# sFMC98_v3.net
KiCad netlist of a schematic drawn in Altium Designer
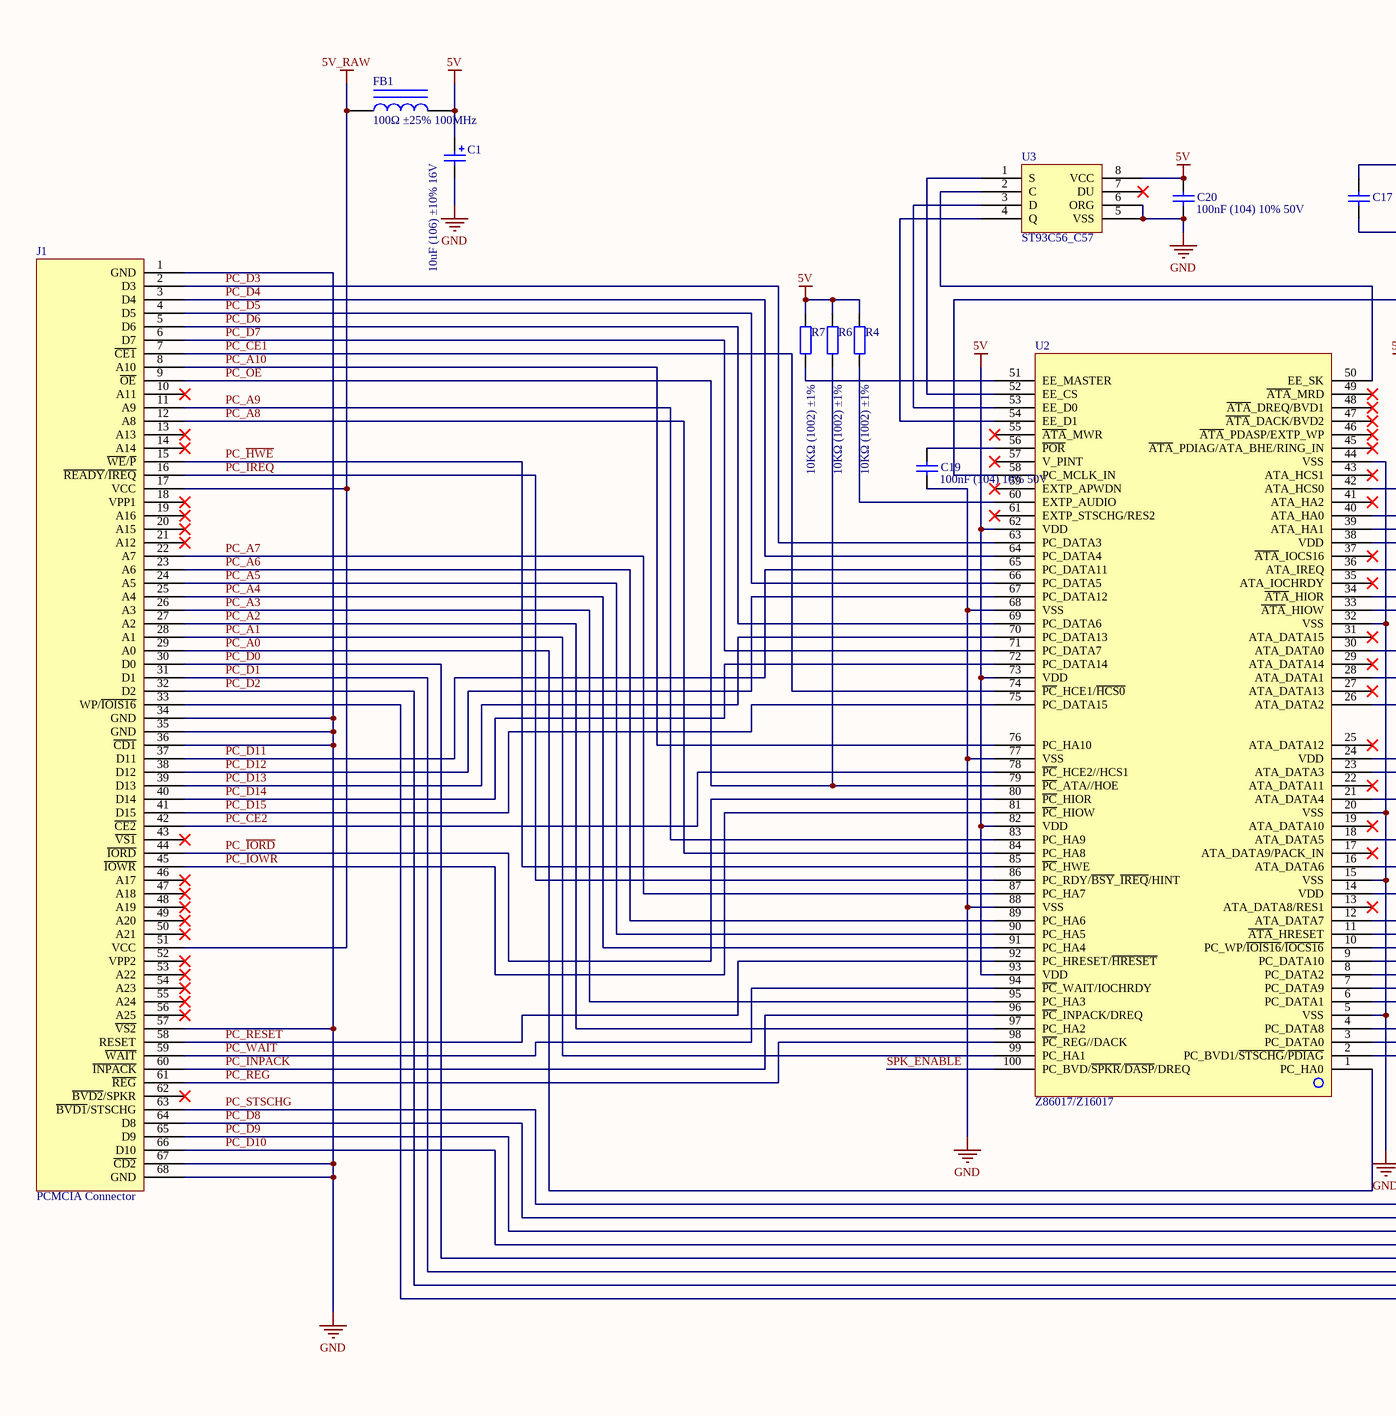
[diagram p0: sFMC98_v3.SchDoc, left]
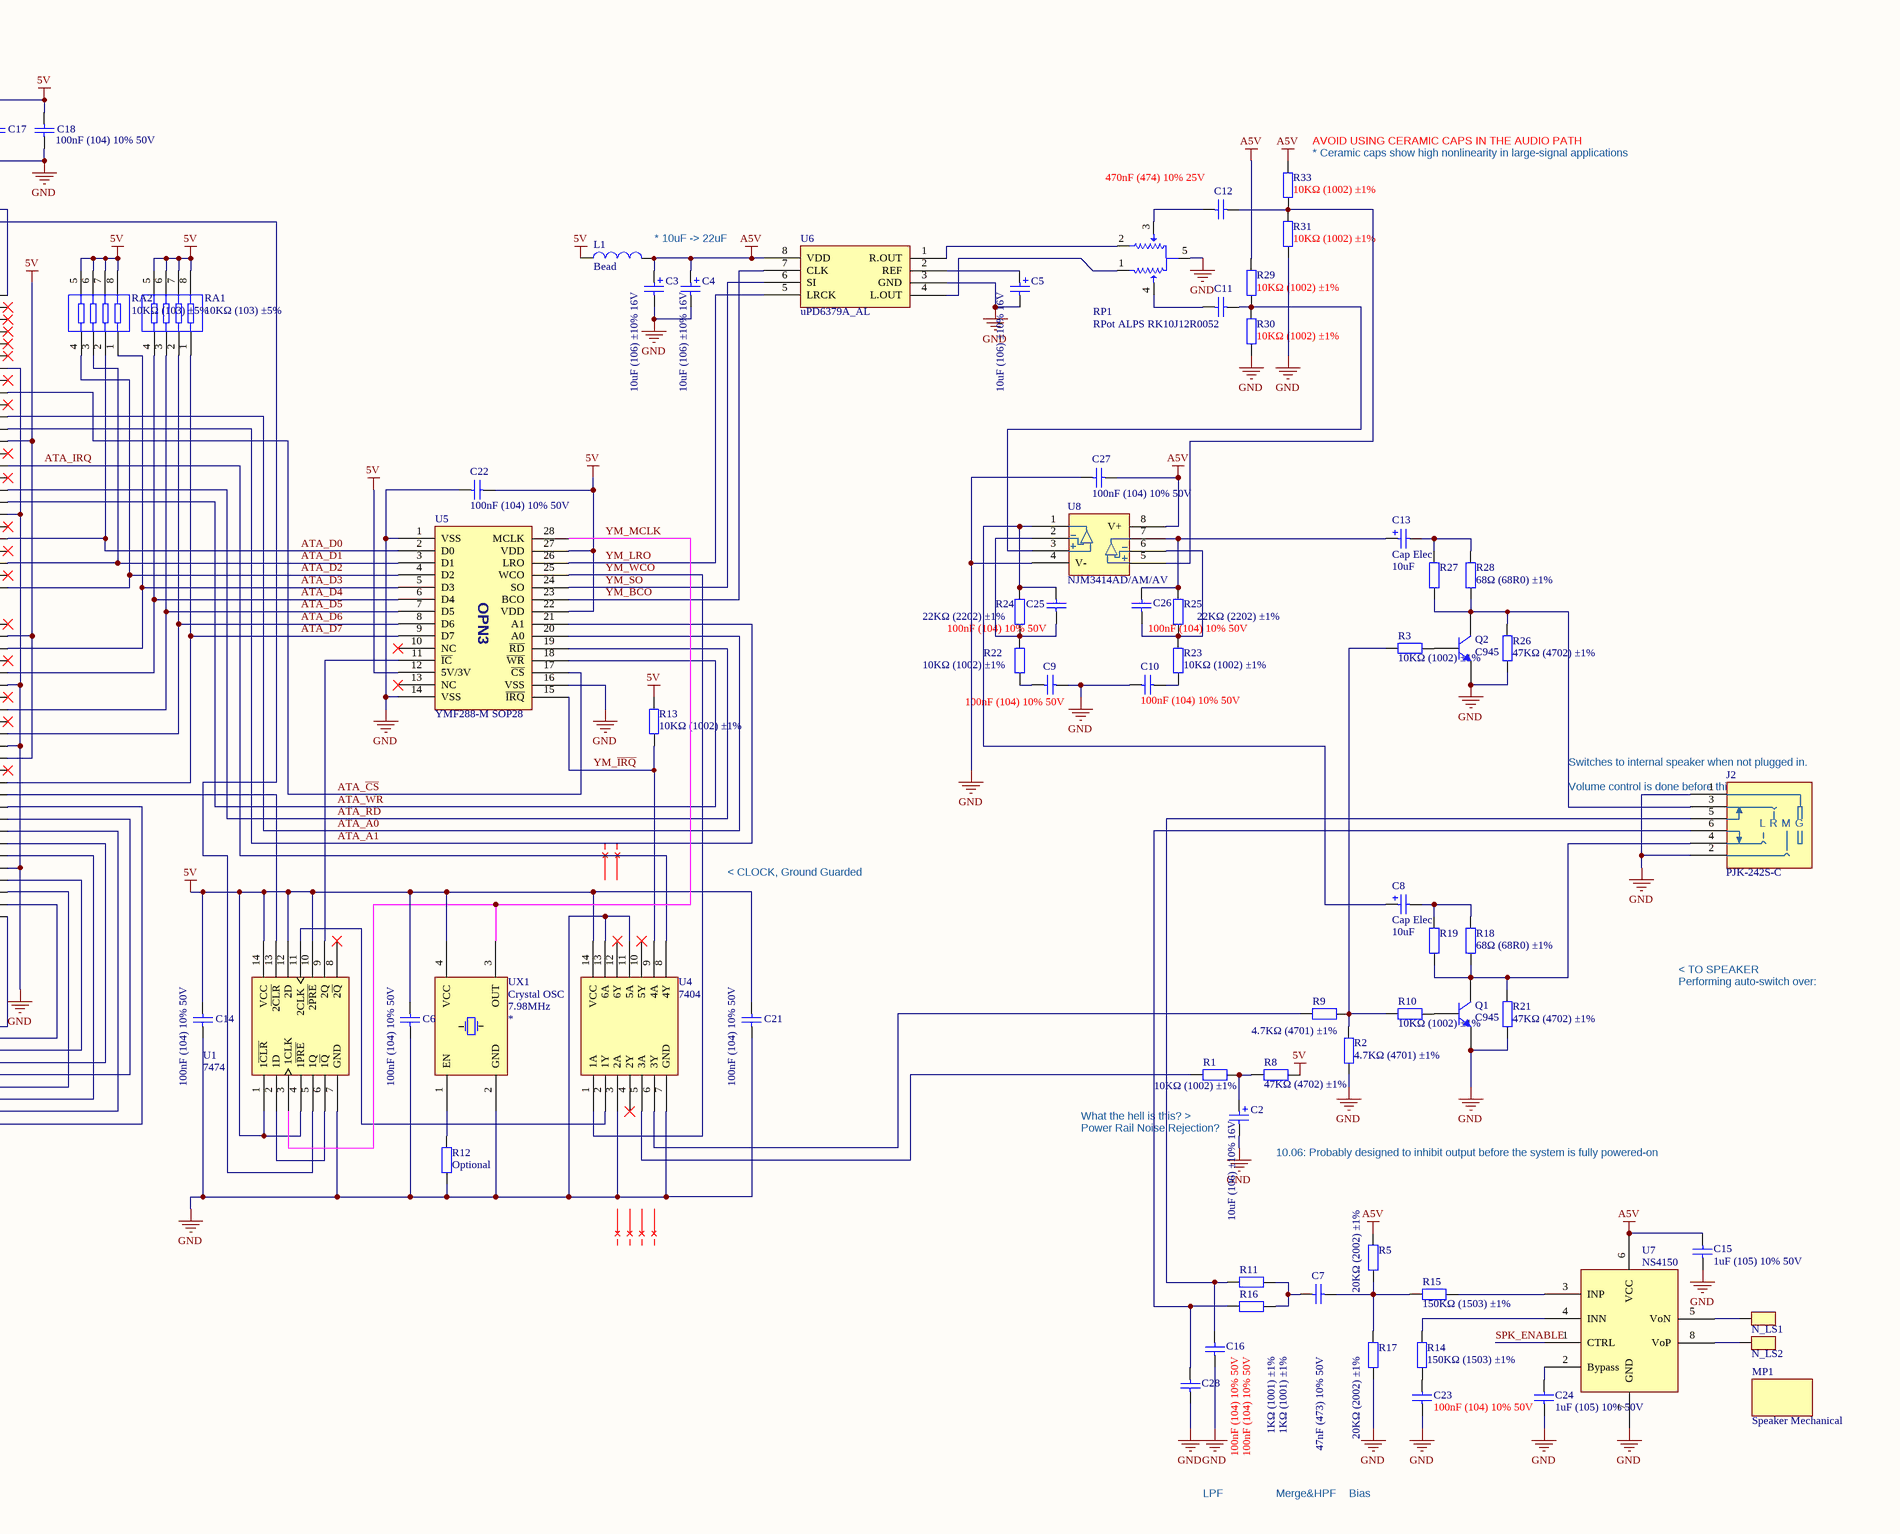
[diagram p1: sFMC98_v3.SchDoc, right]

(export (version "E")
  (design (tool "Eeschema 10.0.6"))
  (components
    (comp (ref "C1")
      (value "10uF (106) ±10% 16V")
      (footprint "CASE-A_3216")
      (description "钽电容")
      (libsource (lib "JLC_Cap") (part "3216 10uF (106) 10% 16V"))
    )
    (comp (ref "C2")
      (value "10uF (106) ±10% 16V")
      (footprint "CASE-A_3216")
      (description "钽电容")
      (libsource (lib "JLC_Cap") (part "3216 10uF (106) 10% 16V"))
    )
    (comp (ref "C3")
      (value "10uF (106) ±10% 16V")
      (footprint "CASE-A_3216")
      (description "钽电容")
      (libsource (lib "JLC_Cap") (part "3216 10uF (106) 10% 16V"))
    )
    (comp (ref "C4")
      (value "10uF (106) ±10% 16V")
      (footprint "CASE-A_3216")
      (description "钽电容")
      (libsource (lib "JLC_Cap") (part "3216 10uF (106) 10% 16V"))
    )
    (comp (ref "C5")
      (value "10uF (106) ±10% 16V")
      (footprint "CASE-A_3216")
      (description "钽电容")
      (libsource (lib "JLC_Cap") (part "3216 10uF (106) 10% 16V"))
    )
    (comp (ref "C6")
      (value "100nF (104) 10% 50V")
      (footprint "0603_C")
      (description "贴片电容")
      (libsource (lib "JLC_Cap") (part "0603 100nF (104) 10% 50V"))
    )
    (comp (ref "C7")
      (value "47nF (473) 10% 50V")
      (footprint "0603_C")
      (description "贴片电容")
      (libsource (lib "JLC_Cap") (part "0603 47nF (473) 10% 50V"))
    )
    (comp (ref "C8")
      (value "Cap Elec")
      (footprint "C-RB-4_5MM_Cutout")
      (description "Polarized Capacitor (Surface Mount)")
      (fields (field (name "ALTIUM_VALUE") "10uF") (field (name "PUBLISHER") "Altium Limited"))
      (libsource (lib "DiscreteRF") (part "Cap Pol3"))
    )
    (comp (ref "C9")
      (value "100nF (104) 10% 50V")
      (footprint "0603_C")
      (description "贴片电容")
      (libsource (lib "JLC_Cap") (part "0603 100nF (104) 10% 50V"))
    )
    (comp (ref "C10")
      (value "100nF (104) 10% 50V")
      (footprint "0603_C")
      (description "贴片电容")
      (libsource (lib "JLC_Cap") (part "0603 100nF (104) 10% 50V"))
    )
    (comp (ref "C11")
      (value "470nF (474) 10% 25V")
      (footprint "0603_C")
      (description "贴片电容")
      (libsource (lib "JLC_Cap") (part "0603 470nF (474) 10% 25V"))
    )
    (comp (ref "C12")
      (value "470nF (474) 10% 25V")
      (footprint "0603_C")
      (description "贴片电容")
      (libsource (lib "JLC_Cap") (part "0603 470nF (474) 10% 25V"))
    )
    (comp (ref "C13")
      (value "Cap Elec")
      (footprint "C-RB-4_5MM_Cutout")
      (description "Polarized Capacitor (Surface Mount)")
      (fields (field (name "ALTIUM_VALUE") "10uF") (field (name "PUBLISHER") "Altium Limited"))
      (libsource (lib "DiscreteRF") (part "Cap Pol3"))
    )
    (comp (ref "C14")
      (value "100nF (104) 10% 50V")
      (footprint "0603_C")
      (description "贴片电容")
      (libsource (lib "JLC_Cap") (part "0603 100nF (104) 10% 50V"))
    )
    (comp (ref "C15")
      (value "1uF (105) 10% 50V")
      (footprint "0603_C")
      (description "贴片电容")
      (libsource (lib "JLC_Cap") (part "0603 1uF (105) 10% 50V"))
    )
    (comp (ref "C16")
      (value "100nF (104) 10% 50V")
      (footprint "0603_C")
      (description "贴片电容")
      (libsource (lib "JLC_Cap") (part "0603 100nF (104) 10% 50V"))
    )
    (comp (ref "C17")
      (value "100nF (104) 10% 50V")
      (footprint "0603_C")
      (description "贴片电容")
      (libsource (lib "JLC_Cap") (part "0603 100nF (104) 10% 50V"))
    )
    (comp (ref "C18")
      (value "100nF (104) 10% 50V")
      (footprint "0603_C")
      (description "贴片电容")
      (libsource (lib "JLC_Cap") (part "0603 100nF (104) 10% 50V"))
    )
    (comp (ref "C19")
      (value "100nF (104) 10% 50V")
      (footprint "0603_C")
      (description "贴片电容")
      (libsource (lib "JLC_Cap") (part "0603 100nF (104) 10% 50V"))
    )
    (comp (ref "C20")
      (value "100nF (104) 10% 50V")
      (footprint "0603_C")
      (description "贴片电容")
      (libsource (lib "JLC_Cap") (part "0603 100nF (104) 10% 50V"))
    )
    (comp (ref "C21")
      (value "100nF (104) 10% 50V")
      (footprint "0603_C")
      (description "贴片电容")
      (libsource (lib "JLC_Cap") (part "0603 100nF (104) 10% 50V"))
    )
    (comp (ref "C22")
      (value "100nF (104) 10% 50V")
      (footprint "0603_C")
      (description "贴片电容")
      (libsource (lib "JLC_Cap") (part "0603 100nF (104) 10% 50V"))
    )
    (comp (ref "C23")
      (value "100nF (104) 10% 50V")
      (footprint "0603_C")
      (description "贴片电容")
      (libsource (lib "JLC_Cap") (part "0603 100nF (104) 10% 50V"))
    )
    (comp (ref "C24")
      (value "1uF (105) 10% 50V")
      (footprint "0603_C")
      (description "贴片电容")
      (libsource (lib "JLC_Cap") (part "0603 1uF (105) 10% 50V"))
    )
    (comp (ref "C25")
      (value "100nF (104) 10% 50V")
      (footprint "0603_C")
      (description "贴片电容")
      (libsource (lib "JLC_Cap") (part "0603 100nF (104) 10% 50V"))
    )
    (comp (ref "C26")
      (value "100nF (104) 10% 50V")
      (footprint "0603_C")
      (description "贴片电容")
      (libsource (lib "JLC_Cap") (part "0603 100nF (104) 10% 50V"))
    )
    (comp (ref "C27")
      (value "100nF (104) 10% 50V")
      (footprint "0603_C")
      (description "贴片电容")
      (libsource (lib "JLC_Cap") (part "0603 100nF (104) 10% 50V"))
    )
    (comp (ref "C28")
      (value "100nF (104) 10% 50V")
      (footprint "0603_C")
      (description "贴片电容")
      (libsource (lib "JLC_Cap") (part "0603 100nF (104) 10% 50V"))
    )
    (comp (ref "FB1")
      (value "100Ω ±25% 100MHz")
      (footprint "0805_L")
      (description "贴片磁珠")
      (libsource (lib "JLC_IUD") (part "0805 100Ω 25% 100MHz"))
    )
    (comp (ref "J1")
      (value "PCMCIA Connector")
      (footprint "PCF-SMT-K1")
      (libsource (lib "PrimaryLIB1") (part "PCMCIA_Conn"))
    )
    (comp (ref "J2")
      (value "PJK-242S-C")
      (footprint "PJK-242S-C")
      (description "2.5mm Headphone Jack")
      (libsource (lib "PrimaryLIB1") (part "PJK-242S-C"))
    )
    (comp (ref "L1")
      (value "Bead")
      (footprint "L2012X10N_LQW21")
      (description "Inductor")
      (fields (field (name "PUBLISHER") "Altium Limited"))
      (libsource (lib "DiscreteRF") (part "Inductor"))
    )
    (comp (ref "MP1")
      (value "Speaker Mechanical")
      (footprint "ZT097")
      (libsource (lib "PrimaryLIB1") (part "Mechanical"))
    )
    (comp (ref "N_LS1")
      (value "PAD")
      (footprint "Pad")
      (description "Generic Pad")
      (libsource (lib "PrimaryLIB0") (part "PAD"))
    )
    (comp (ref "N_LS2")
      (value "PAD")
      (footprint "Pad")
      (description "Generic Pad")
      (libsource (lib "PrimaryLIB0") (part "PAD"))
    )
    (comp (ref "Q1")
      (value "C945")
      (footprint "SOT-23(SOT-23-3)")
      (description "三极管")
      (libsource (lib "JLC_Transistor_NPN") (part "SOT-23 SS8050 Y1"))
    )
    (comp (ref "Q2")
      (value "C945")
      (footprint "SOT-23(SOT-23-3)")
      (description "三极管")
      (libsource (lib "JLC_Transistor_NPN") (part "SOT-23 SS8050 Y1"))
    )
    (comp (ref "R1")
      (value "10KΩ (1002) ±1%")
      (footprint "0603_R")
      (description "贴片电阻")
      (libsource (lib "") (part "0603 10KΩ (1002) 1%_1"))
    )
    (comp (ref "R2")
      (value "4.7KΩ (4701) ±1%")
      (footprint "0603_R")
      (description "贴片电阻")
      (libsource (lib "") (part "0603 4.7KΩ (4701) 1%_1"))
    )
    (comp (ref "R3")
      (value "10KΩ (1002) ±1%")
      (footprint "0603_R")
      (description "贴片电阻")
      (libsource (lib "") (part "0603 10KΩ (1002) 1%_1"))
    )
    (comp (ref "R4")
      (value "10KΩ (1002) ±1%")
      (footprint "0603_R")
      (description "贴片电阻")
      (libsource (lib "JLC_RES") (part "0603 10KΩ (1002) 1%"))
    )
    (comp (ref "R5")
      (value "20KΩ (2002) ±1%")
      (footprint "0603_R")
      (description "贴片电阻")
      (libsource (lib "JLC_RES") (part "0603 20KΩ (2002) 1%"))
    )
    (comp (ref "R6")
      (value "10KΩ (1002) ±1%")
      (footprint "0603_R")
      (description "贴片电阻")
      (libsource (lib "JLC_RES") (part "0603 10KΩ (1002) 1%"))
    )
    (comp (ref "R7")
      (value "10KΩ (1002) ±1%")
      (footprint "0603_R")
      (description "贴片电阻")
      (libsource (lib "JLC_RES") (part "0603 10KΩ (1002) 1%"))
    )
    (comp (ref "R8")
      (value "47KΩ (4702) ±1%")
      (footprint "0603_R")
      (description "贴片电阻")
      (libsource (lib "") (part "0603 47KΩ (4702) 1%_1"))
    )
    (comp (ref "R9")
      (value "4.7KΩ (4701) ±1%")
      (footprint "0603_R")
      (description "贴片电阻")
      (libsource (lib "JLC_RES") (part "0603 4.7KΩ (4701) 1%"))
    )
    (comp (ref "R10")
      (value "10KΩ (1002) ±1%")
      (footprint "0603_R")
      (description "贴片电阻")
      (libsource (lib "") (part "0603 10KΩ (1002) 1%_1"))
    )
    (comp (ref "R11")
      (value "1KΩ (1001) ±1%")
      (footprint "0603_R")
      (description "贴片电阻")
      (libsource (lib "JLC_RES") (part "0603 1KΩ (1001) 1%"))
    )
    (comp (ref "R12")
      (value "Optional")
      (footprint "0603_R")
      (description "贴片电阻")
      (libsource (lib "JLC_RES") (part "0603 10KΩ (1002) 1%"))
    )
    (comp (ref "R13")
      (value "10KΩ (1002) ±1%")
      (footprint "0603_R")
      (description "贴片电阻")
      (libsource (lib "JLC_RES") (part "0603 10KΩ (1002) 1%"))
    )
    (comp (ref "R14")
      (value "150KΩ (1503) ±1%")
      (footprint "0603_R")
      (description "贴片电阻")
      (libsource (lib "JLC_RES") (part "0603 150KΩ (1503) 1%"))
    )
    (comp (ref "R15")
      (value "150KΩ (1503) ±1%")
      (footprint "0603_R")
      (description "贴片电阻")
      (libsource (lib "") (part "0603 150KΩ (1503) 1%_1"))
    )
    (comp (ref "R16")
      (value "1KΩ (1001) ±1%")
      (footprint "0603_R")
      (description "贴片电阻")
      (libsource (lib "JLC_RES") (part "0603 1KΩ (1001) 1%"))
    )
    (comp (ref "R17")
      (value "20KΩ (2002) ±1%")
      (footprint "0603_R")
      (description "贴片电阻")
      (libsource (lib "JLC_RES") (part "0603 20KΩ (2002) 1%"))
    )
    (comp (ref "R18")
      (value "68Ω (68R0) ±1%")
      (footprint "0603_R")
      (description "贴片电阻")
      (libsource (lib "JLC_RES") (part "0603 68Ω (68R0) 1%"))
    )
    (comp (ref "R19")
      (value "68Ω (68R0) ±1%")
      (footprint "0603_R")
      (description "贴片电阻")
      (libsource (lib "JLC_RES") (part "0603 68Ω (68R0) 1%"))
    )
    (comp (ref "R21")
      (value "47KΩ (4702) ±1%")
      (footprint "0603_R")
      (description "贴片电阻")
      (libsource (lib "JLC_RES") (part "0603 47KΩ (4702) 1%"))
    )
    (comp (ref "R22")
      (value "10KΩ (1002) ±1%")
      (footprint "0603_R")
      (description "贴片电阻")
      (libsource (lib "JLC_RES") (part "0603 10KΩ (1002) 1%"))
    )
    (comp (ref "R23")
      (value "10KΩ (1002) ±1%")
      (footprint "0603_R")
      (description "贴片电阻")
      (libsource (lib "JLC_RES") (part "0603 10KΩ (1002) 1%"))
    )
    (comp (ref "R24")
      (value "22KΩ (2202) ±1%")
      (footprint "0603_R")
      (description "贴片电阻")
      (libsource (lib "JLC_RES") (part "0603 22KΩ (2202) 1%"))
    )
    (comp (ref "R25")
      (value "22KΩ (2202) ±1%")
      (footprint "0603_R")
      (description "贴片电阻")
      (libsource (lib "JLC_RES") (part "0603 22KΩ (2202) 1%"))
    )
    (comp (ref "R26")
      (value "47KΩ (4702) ±1%")
      (footprint "0603_R")
      (description "贴片电阻")
      (libsource (lib "JLC_RES") (part "0603 47KΩ (4702) 1%"))
    )
    (comp (ref "R27")
      (value "68Ω (68R0) ±1%")
      (footprint "0603_R")
      (description "贴片电阻")
      (libsource (lib "JLC_RES") (part "0603 68Ω (68R0) 1%"))
    )
    (comp (ref "R28")
      (value "68Ω (68R0) ±1%")
      (footprint "0603_R")
      (description "贴片电阻")
      (libsource (lib "JLC_RES") (part "0603 68Ω (68R0) 1%"))
    )
    (comp (ref "R29")
      (value "10KΩ (1002) ±1%")
      (footprint "0603_R")
      (description "贴片电阻")
      (libsource (lib "JLC_RES") (part "0603 10KΩ (1002) 1%"))
    )
    (comp (ref "R30")
      (value "10KΩ (1002) ±1%")
      (footprint "0603_R")
      (description "贴片电阻")
      (libsource (lib "JLC_RES") (part "0603 10KΩ (1002) 1%"))
    )
    (comp (ref "R31")
      (value "10KΩ (1002) ±1%")
      (footprint "0603_R")
      (description "贴片电阻")
      (libsource (lib "JLC_RES") (part "0603 10KΩ (1002) 1%"))
    )
    (comp (ref "R33")
      (value "10KΩ (1002) ±1%")
      (footprint "0603_R")
      (description "贴片电阻")
      (libsource (lib "JLC_RES") (part "0603 10KΩ (1002) 1%"))
    )
    (comp (ref "RA1")
      (value "10KΩ (103) ±5%")
      (footprint "0603_Rx4")
      (description "贴片排阻")
      (libsource (lib "JLC_RES") (part "0603*4  10KΩ (103) 5%"))
    )
    (comp (ref "RA2")
      (value "10KΩ (103) ±5%")
      (footprint "0603_Rx4")
      (description "贴片排阻")
      (libsource (lib "JLC_RES") (part "0603*4  10KΩ (103) 5%"))
    )
    (comp (ref "RP1")
      (value "RPot ALPS RK10J12R0052")
      (footprint "RPot_RK10J12R_ALPS")
      (description "ALPS Taper Type C, Dual Unit")
      (libsource (lib "PrimaryLIB1") (part "RPot_ALPS_C2"))
    )
    (comp (ref "U1")
      (value "7474")
      (footprint "TSSOP14_TSOP65P640X120-14N")
      (description "Dual D-Type Positive-Edge-Triggered Flip-Flops With Preset And Clear")
      (libsource (lib "7400") (part "7474_J_N_1"))
    )
    (comp (ref "U2")
      (value "Z86017/Z16017")
      (footprint "VQFP100_TSQFP50P1600X1600X160-100N")
      (libsource (lib "PrimaryLIB1") (part "ZX6017"))
    )
    (comp (ref "U3")
      (value "ST93C56_C57")
      (footprint "SOIC-8 NB")
      (description "2K (128 x 16 or 256 x 8) SERIAL MICROWIRE EEPROM")
      (libsource (lib "PrimaryLIB1") (part "ST93C56_C57"))
    )
    (comp (ref "U4")
      (value "7404")
      (footprint "TSSOP14_TSOP65P640X120-14N")
      (description "Hex Inverter")
      (libsource (lib "7400") (part "7404_J_N_1"))
    )
    (comp (ref "U5")
      (value "YMF288-M SOP28")
      (footprint "SOP127P1030X265-28N")
      (libsource (lib "Audio") (part "YMF288_M"))
    )
    (comp (ref "U6")
      (value "uPD6379A_AL")
      (footprint "DMP8_SOIC127P680X175-8N")
      (description "2-CHANNEL 16-BIT D/A CONVERTER FOR AUDIO APPLICATION")
      (libsource (lib "Audio") (part "uPD6379A_AL"))
    )
    (comp (ref "U7")
      (value "NS4150")
      (footprint "MS8")
      (description "超低 EMI、无需滤波器、3W 单声道 D 类音频功放")
      (libsource (lib "PrimaryLIB1") (part "NS4150"))
    )
    (comp (ref "U8")
      (value "NJM3414AD/AM/AV")
      (footprint "DMP8_SOIC127P680X175-8N")
      (description "Single-Supply Dual High Current Operational Amplifier")
      (libsource (lib "PrimaryLIB1") (part "NJM3414AD_AM_AV_1"))
    )
    (comp (ref "UX1")
      (value "Crystal OSC")
      (footprint "SMD-3225_4P")
      (fields (field (name "FREQ") "7.98MHz") (field (name "TYPE") "*"))
      (libsource (lib "PrimaryLIB1") (part "XTAL_OSC"))
    )
  )
  (nets
    (net (code "1") (name "/ATA_A0") (class "Default")
      (node (ref "U2") (pin "40") (pinfunction "ATA_HA0_40") (pintype "passive"))
      (node (ref "U5") (pin "20") (pinfunction "A0_20") (pintype "passive"))
    )
    (net (code "2") (name "/ATA_A1") (class "Default")
      (node (ref "U2") (pin "39") (pinfunction "ATA_HA1_39") (pintype "passive"))
      (node (ref "U5") (pin "21") (pinfunction "A1_21") (pintype "passive"))
    )
    (net (code "3") (name "/ATA_D0") (class "Default")
      (node (ref "RA2") (pin "2") (pinfunction "2_2") (pintype "passive"))
      (node (ref "U2") (pin "30") (pinfunction "ATA_DATA0_30") (pintype "passive"))
      (node (ref "U5") (pin "2") (pinfunction "D0_2") (pintype "passive"))
    )
    (net (code "4") (name "/ATA_D1") (class "Default")
      (node (ref "RA2") (pin "3") (pinfunction "3_3") (pintype "passive"))
      (node (ref "U2") (pin "28") (pinfunction "ATA_DATA1_28") (pintype "passive"))
      (node (ref "U5") (pin "3") (pinfunction "D1_3") (pintype "passive"))
    )
    (net (code "5") (name "/ATA_D2") (class "Default")
      (node (ref "RA2") (pin "4") (pinfunction "4_4") (pintype "passive"))
      (node (ref "U2") (pin "26") (pinfunction "ATA_DATA2_26") (pintype "passive"))
      (node (ref "U5") (pin "4") (pinfunction "D2_4") (pintype "passive"))
    )
    (net (code "6") (name "/ATA_D3") (class "Default")
      (node (ref "RA2") (pin "1") (pinfunction "1_1") (pintype "passive"))
      (node (ref "U2") (pin "23") (pinfunction "ATA_DATA3_23") (pintype "passive"))
      (node (ref "U5") (pin "5") (pinfunction "D3_5") (pintype "passive"))
    )
    (net (code "7") (name "/ATA_D4") (class "Default")
      (node (ref "RA1") (pin "4") (pinfunction "4_4") (pintype "passive"))
      (node (ref "U2") (pin "21") (pinfunction "ATA_DATA4_21") (pintype "passive"))
      (node (ref "U5") (pin "6") (pinfunction "D4_6") (pintype "passive"))
    )
    (net (code "8") (name "/ATA_D5") (class "Default")
      (node (ref "RA1") (pin "3") (pinfunction "3_3") (pintype "passive"))
      (node (ref "U2") (pin "18") (pinfunction "ATA_DATA5_18") (pintype "passive"))
      (node (ref "U5") (pin "7") (pinfunction "D5_7") (pintype "passive"))
    )
    (net (code "9") (name "/ATA_D6") (class "Default")
      (node (ref "RA1") (pin "2") (pinfunction "2_2") (pintype "passive"))
      (node (ref "U2") (pin "16") (pinfunction "ATA_DATA6_16") (pintype "passive"))
      (node (ref "U5") (pin "8") (pinfunction "D6_8") (pintype "passive"))
    )
    (net (code "10") (name "/ATA_D7") (class "Default")
      (node (ref "RA1") (pin "1") (pinfunction "1_1") (pintype "passive"))
      (node (ref "U2") (pin "12") (pinfunction "ATA_DATA7_12") (pintype "passive"))
      (node (ref "U5") (pin "9") (pinfunction "D7_9") (pintype "passive"))
    )
    (net (code "11") (name "/ATA_IRQ") (class "Default")
      (node (ref "U2") (pin "36") (pinfunction "ATA_IREQ_36") (pintype "passive"))
      (node (ref "U4") (pin "8") (pinfunction "4Y_8") (pintype "passive"))
    )
    (net (code "12") (name "/ATA_~{CS}") (class "Default")
      (node (ref "U2") (pin "42") (pinfunction "ATA_HCS0_42") (pintype "passive"))
      (node (ref "U5") (pin "17") (pinfunction "~{CS}_17") (pintype "passive"))
    )
    (net (code "13") (name "/ATA_~{RD}") (class "Default")
      (node (ref "U2") (pin "34") (pinfunction "~{ATA}_HIOR_34") (pintype "passive"))
      (node (ref "U5") (pin "19") (pinfunction "~{RD}_19") (pintype "passive"))
    )
    (net (code "14") (name "/ATA_~{WR}") (class "Default")
      (node (ref "U2") (pin "33") (pinfunction "~{ATA}_HIOW_33") (pintype "passive"))
      (node (ref "U5") (pin "18") (pinfunction "~{WR}_18") (pintype "passive"))
    )
    (net (code "15") (name "/PC_A0") (class "Default")
      (node (ref "J1") (pin "29") (pinfunction "A0_29") (pintype "passive"))
      (node (ref "U2") (pin "1") (pinfunction "PC_HA0_1") (pintype "passive"))
    )
    (net (code "16") (name "/PC_A1") (class "Default")
      (node (ref "J1") (pin "28") (pinfunction "A1_28") (pintype "passive"))
      (node (ref "U2") (pin "99") (pinfunction "PC_HA1_99") (pintype "passive"))
    )
    (net (code "17") (name "/PC_A2") (class "Default")
      (node (ref "J1") (pin "27") (pinfunction "A2_27") (pintype "passive"))
      (node (ref "U2") (pin "97") (pinfunction "PC_HA2_97") (pintype "passive"))
    )
    (net (code "18") (name "/PC_A3") (class "Default")
      (node (ref "J1") (pin "26") (pinfunction "A3_26") (pintype "passive"))
      (node (ref "U2") (pin "95") (pinfunction "PC_HA3_95") (pintype "passive"))
    )
    (net (code "19") (name "/PC_A4") (class "Default")
      (node (ref "J1") (pin "25") (pinfunction "A4_25") (pintype "passive"))
      (node (ref "U2") (pin "91") (pinfunction "PC_HA4_91") (pintype "passive"))
    )
    (net (code "20") (name "/PC_A5") (class "Default")
      (node (ref "J1") (pin "24") (pinfunction "A5_24") (pintype "passive"))
      (node (ref "U2") (pin "90") (pinfunction "PC_HA5_90") (pintype "passive"))
    )
    (net (code "21") (name "/PC_A6") (class "Default")
      (node (ref "J1") (pin "23") (pinfunction "A6_23") (pintype "passive"))
      (node (ref "U2") (pin "89") (pinfunction "PC_HA6_89") (pintype "passive"))
    )
    (net (code "22") (name "/PC_A7") (class "Default")
      (node (ref "J1") (pin "22") (pinfunction "A7_22") (pintype "passive"))
      (node (ref "U2") (pin "87") (pinfunction "PC_HA7_87") (pintype "passive"))
    )
    (net (code "23") (name "/PC_A8") (class "Default")
      (node (ref "J1") (pin "12") (pinfunction "A8_12") (pintype "passive"))
      (node (ref "U2") (pin "84") (pinfunction "PC_HA8_84") (pintype "passive"))
    )
    (net (code "24") (name "/PC_A9") (class "Default")
      (node (ref "J1") (pin "11") (pinfunction "A9_11") (pintype "passive"))
      (node (ref "U2") (pin "83") (pinfunction "PC_HA9_83") (pintype "passive"))
    )
    (net (code "25") (name "/PC_A10") (class "Default")
      (node (ref "J1") (pin "8") (pinfunction "A10_8") (pintype "passive"))
      (node (ref "U2") (pin "76") (pinfunction "PC_HA10_76") (pintype "passive"))
    )
    (net (code "26") (name "/PC_D0") (class "Default")
      (node (ref "J1") (pin "30") (pinfunction "D0_30") (pintype "passive"))
      (node (ref "U2") (pin "3") (pinfunction "PC_DATA0_3") (pintype "passive"))
    )
    (net (code "27") (name "/PC_D1") (class "Default")
      (node (ref "J1") (pin "31") (pinfunction "D1_31") (pintype "passive"))
      (node (ref "U2") (pin "6") (pinfunction "PC_DATA1_6") (pintype "passive"))
    )
    (net (code "28") (name "/PC_D2") (class "Default")
      (node (ref "J1") (pin "32") (pinfunction "D2_32") (pintype "passive"))
      (node (ref "U2") (pin "8") (pinfunction "PC_DATA2_8") (pintype "passive"))
    )
    (net (code "29") (name "/PC_D3") (class "Default")
      (node (ref "J1") (pin "2") (pinfunction "D3_2") (pintype "passive"))
      (node (ref "U2") (pin "63") (pinfunction "PC_DATA3_63") (pintype "passive"))
    )
    (net (code "30") (name "/PC_D4") (class "Default")
      (node (ref "J1") (pin "3") (pinfunction "D4_3") (pintype "passive"))
      (node (ref "U2") (pin "64") (pinfunction "PC_DATA4_64") (pintype "passive"))
    )
    (net (code "31") (name "/PC_D5") (class "Default")
      (node (ref "J1") (pin "4") (pinfunction "D5_4") (pintype "passive"))
      (node (ref "U2") (pin "66") (pinfunction "PC_DATA5_66") (pintype "passive"))
    )
    (net (code "32") (name "/PC_D6") (class "Default")
      (node (ref "J1") (pin "5") (pinfunction "D6_5") (pintype "passive"))
      (node (ref "U2") (pin "69") (pinfunction "PC_DATA6_69") (pintype "passive"))
    )
    (net (code "33") (name "/PC_D7") (class "Default")
      (node (ref "J1") (pin "6") (pinfunction "D7_6") (pintype "passive"))
      (node (ref "U2") (pin "71") (pinfunction "PC_DATA7_71") (pintype "passive"))
    )
    (net (code "34") (name "/PC_D8") (class "Default")
      (node (ref "J1") (pin "64") (pinfunction "D8_64") (pintype "passive"))
      (node (ref "U2") (pin "4") (pinfunction "PC_DATA8_4") (pintype "passive"))
    )
    (net (code "35") (name "/PC_D9") (class "Default")
      (node (ref "J1") (pin "65") (pinfunction "D9_65") (pintype "passive"))
      (node (ref "U2") (pin "7") (pinfunction "PC_DATA9_7") (pintype "passive"))
    )
    (net (code "36") (name "/PC_D10") (class "Default")
      (node (ref "J1") (pin "66") (pinfunction "D10_66") (pintype "passive"))
      (node (ref "U2") (pin "9") (pinfunction "PC_DATA10_9") (pintype "passive"))
    )
    (net (code "37") (name "/PC_D11") (class "Default")
      (node (ref "J1") (pin "37") (pinfunction "D11_37") (pintype "passive"))
      (node (ref "U2") (pin "65") (pinfunction "PC_DATA11_65") (pintype "passive"))
    )
    (net (code "38") (name "/PC_D12") (class "Default")
      (node (ref "J1") (pin "38") (pinfunction "D12_38") (pintype "passive"))
      (node (ref "U2") (pin "67") (pinfunction "PC_DATA12_67") (pintype "passive"))
    )
    (net (code "39") (name "/PC_D13") (class "Default")
      (node (ref "J1") (pin "39") (pinfunction "D13_39") (pintype "passive"))
      (node (ref "U2") (pin "70") (pinfunction "PC_DATA13_70") (pintype "passive"))
    )
    (net (code "40") (name "/PC_D14") (class "Default")
      (node (ref "J1") (pin "40") (pinfunction "D14_40") (pintype "passive"))
      (node (ref "U2") (pin "72") (pinfunction "PC_DATA14_72") (pintype "passive"))
    )
    (net (code "41") (name "/PC_D15") (class "Default")
      (node (ref "J1") (pin "41") (pinfunction "D15_41") (pintype "passive"))
      (node (ref "U2") (pin "75") (pinfunction "PC_DATA15_75") (pintype "passive"))
    )
    (net (code "42") (name "/PC_RESET") (class "Default")
      (node (ref "J1") (pin "58") (pinfunction "RESET_58") (pintype "passive"))
      (node (ref "U2") (pin "92") (pinfunction "PC_HRESET/~{HRESET}_92") (pintype "passive"))
    )
    (net (code "43") (name "/PC_STSCHG") (class "Default")
      (node (ref "J1") (pin "63") (pinfunction "~{BVD1}/STSCHG_63") (pintype "passive"))
      (node (ref "U2") (pin "2") (pinfunction "PC_BVD1/~{STSCHG}/~{PDIAG}_2") (pintype "passive"))
    )
    (net (code "44") (name "/PC_~{CE1}") (class "Default")
      (node (ref "J1") (pin "7") (pinfunction "~{CE1}_7") (pintype "passive"))
      (node (ref "U2") (pin "74") (pinfunction "~{PC}_HCE1/~{HCS0}_74") (pintype "passive"))
    )
    (net (code "45") (name "/PC_~{CE2}") (class "Default")
      (node (ref "J1") (pin "42") (pinfunction "~{CE2}_42") (pintype "passive"))
      (node (ref "U2") (pin "78") (pinfunction "~{PC}_HCE2//HCS1_78") (pintype "passive"))
    )
    (net (code "46") (name "/PC_~{HWE}") (class "Default")
      (node (ref "J1") (pin "15") (pinfunction "~{WE}/~{P}_15") (pintype "passive"))
      (node (ref "U2") (pin "85") (pinfunction "~{PC}_HWE_85") (pintype "passive"))
    )
    (net (code "47") (name "/PC_~{INPACK}") (class "Default")
      (node (ref "J1") (pin "60") (pinfunction "~{INPACK}_60") (pintype "passive"))
      (node (ref "U2") (pin "96") (pinfunction "~{PC}_INPACK/DREQ_96") (pintype "passive"))
    )
    (net (code "48") (name "/PC_~{IORD}") (class "Default")
      (node (ref "J1") (pin "44") (pinfunction "~{IORD}_44") (pintype "passive"))
      (node (ref "U2") (pin "80") (pinfunction "~{PC}_HIOR_80") (pintype "passive"))
    )
    (net (code "49") (name "/PC_~{IOWR}") (class "Default")
      (node (ref "J1") (pin "45") (pinfunction "~{IOWR}_45") (pintype "passive"))
      (node (ref "U2") (pin "81") (pinfunction "~{PC}_HIOW_81") (pintype "passive"))
    )
    (net (code "50") (name "/PC_~{IREQ}") (class "Default")
      (node (ref "J1") (pin "16") (pinfunction "~{READY}/~{IREQ}_16") (pintype "passive"))
      (node (ref "U2") (pin "86") (pinfunction "PC_RDY/~{BSY}_~{IREQ}/HINT_86") (pintype "passive"))
    )
    (net (code "51") (name "/PC_~{OE}") (class "Default")
      (node (ref "J1") (pin "9") (pinfunction "~{OE}_9") (pintype "passive"))
      (node (ref "R6") (pin "1") (pinfunction "1_1") (pintype "passive"))
      (node (ref "U2") (pin "79") (pinfunction "~{PC}_ATA//HOE_79") (pintype "passive"))
    )
    (net (code "52") (name "/PC_~{REG}") (class "Default")
      (node (ref "J1") (pin "61") (pinfunction "~{REG}_61") (pintype "passive"))
      (node (ref "U2") (pin "98") (pinfunction "~{PC}_REG//DACK_98") (pintype "passive"))
    )
    (net (code "53") (name "/PC_~{WAIT}") (class "Default")
      (node (ref "J1") (pin "59") (pinfunction "~{WAIT}_59") (pintype "passive"))
      (node (ref "U2") (pin "94") (pinfunction "~{PC}_WAIT/IOCHRDY_94") (pintype "passive"))
    )
    (net (code "54") (name "/SPK_ENABLE") (class "Default")
      (node (ref "U2") (pin "100") (pinfunction "PC_BVD/~{SPKR}/~{DASP}/DREQ_100") (pintype "passive"))
      (node (ref "U7") (pin "1") (pinfunction "CTRL_1") (pintype "passive"))
    )
    (net (code "55") (name "/YM_BCO") (class "Default")
      (node (ref "U5") (pin "23") (pinfunction "BCO_23") (pintype "passive"))
      (node (ref "U6") (pin "7") (pinfunction "CLK_7") (pintype "passive"))
    )
    (net (code "56") (name "/YM_LRO") (class "Default")
      (node (ref "U5") (pin "26") (pinfunction "LRO_26") (pintype "passive"))
      (node (ref "U6") (pin "5") (pinfunction "LRCK_5") (pintype "passive"))
    )
    (net (code "57") (name "/YM_MCLK") (class "Default")
      (node (ref "U1") (pin "3") (pinfunction "1CLK_3") (pintype "passive"))
      (node (ref "U5") (pin "28") (pinfunction "MCLK_28") (pintype "passive"))
      (node (ref "UX1") (pin "3") (pinfunction "OUT_3") (pintype "passive"))
    )
    (net (code "58") (name "/YM_SO") (class "Default")
      (node (ref "U5") (pin "24") (pinfunction "SO_24") (pintype "passive"))
      (node (ref "U6") (pin "6") (pinfunction "SI_6") (pintype "passive"))
    )
    (net (code "59") (name "/YM_WCO") (class "Default")
      (node (ref "U4") (pin "1") (pinfunction "1A_1") (pintype "passive"))
      (node (ref "U5") (pin "25") (pinfunction "WCO_25") (pintype "passive"))
    )
    (net (code "60") (name "/YM_~{IRQ}") (class "Default")
      (node (ref "R13") (pin "1") (pinfunction "1_1") (pintype "passive"))
      (node (ref "U4") (pin "9") (pinfunction "4A_9") (pintype "passive"))
      (node (ref "U5") (pin "15") (pinfunction "~{IRQ}_15") (pintype "passive"))
    )
    (net (code "61") (name "5V") (class "Default")
      (node (ref "C1") (pin "1") (pinfunction "1_1") (pintype "passive"))
      (node (ref "C14") (pin "2") (pinfunction "2_2") (pintype "passive"))
      (node (ref "C17") (pin "2") (pinfunction "2_2") (pintype "passive"))
      (node (ref "C18") (pin "2") (pinfunction "2_2") (pintype "passive"))
      (node (ref "C20") (pin "2") (pinfunction "2_2") (pintype "passive"))
      (node (ref "C21") (pin "2") (pinfunction "2_2") (pintype "passive"))
      (node (ref "C22") (pin "1") (pinfunction "1_1") (pintype "passive"))
      (node (ref "C6") (pin "2") (pinfunction "2_2") (pintype "passive"))
      (node (ref "FB1") (pin "2") (pinfunction "2_2") (pintype "passive"))
      (node (ref "L1") (pin "2") (pinfunction "2_2") (pintype "passive"))
      (node (ref "R13") (pin "2") (pinfunction "2_2") (pintype "passive"))
      (node (ref "R4") (pin "2") (pinfunction "2_2") (pintype "passive"))
      (node (ref "R6") (pin "2") (pinfunction "2_2") (pintype "passive"))
      (node (ref "R7") (pin "2") (pinfunction "2_2") (pintype "passive"))
      (node (ref "R8") (pin "1") (pinfunction "1_1") (pintype "passive"))
      (node (ref "RA1") (pin "5") (pinfunction "5_5") (pintype "passive"))
      (node (ref "RA1") (pin "6") (pinfunction "6_6") (pintype "passive"))
      (node (ref "RA1") (pin "7") (pinfunction "7_7") (pintype "passive"))
      (node (ref "RA1") (pin "8") (pinfunction "8_8") (pintype "passive"))
      (node (ref "RA2") (pin "5") (pinfunction "5_5") (pintype "passive"))
      (node (ref "RA2") (pin "6") (pinfunction "6_6") (pintype "passive"))
      (node (ref "RA2") (pin "7") (pinfunction "7_7") (pintype "passive"))
      (node (ref "RA2") (pin "8") (pinfunction "8_8") (pintype "passive"))
      (node (ref "U1") (pin "1") (pinfunction "1~{CLR}_1") (pintype "passive"))
      (node (ref "U1") (pin "10") (pinfunction "2~{PRE}_10") (pintype "passive"))
      (node (ref "U1") (pin "12") (pinfunction "2D_12") (pintype "passive"))
      (node (ref "U1") (pin "14") (pinfunction "VCC_14") (pintype "passive"))
      (node (ref "U1") (pin "4") (pinfunction "1~{PRE}_4") (pintype "passive"))
      (node (ref "U2") (pin "14") (pinfunction "VDD_14") (pintype "passive"))
      (node (ref "U2") (pin "24") (pinfunction "VDD_24") (pintype "passive"))
      (node (ref "U2") (pin "38") (pinfunction "VDD_38") (pintype "passive"))
      (node (ref "U2") (pin "62") (pinfunction "VDD_62") (pintype "passive"))
      (node (ref "U2") (pin "73") (pinfunction "VDD_73") (pintype "passive"))
      (node (ref "U2") (pin "82") (pinfunction "VDD_82") (pintype "passive"))
      (node (ref "U2") (pin "93") (pinfunction "VDD_93") (pintype "passive"))
      (node (ref "U3") (pin "8") (pinfunction "VCC_8") (pintype "passive"))
      (node (ref "U4") (pin "14") (pinfunction "VCC_14") (pintype "passive"))
      (node (ref "U5") (pin "12") (pinfunction "5V/3V_12") (pintype "passive"))
      (node (ref "U5") (pin "22") (pinfunction "VDD_22") (pintype "passive"))
      (node (ref "U5") (pin "27") (pinfunction "VDD_27") (pintype "passive"))
      (node (ref "UX1") (pin "4") (pinfunction "VCC_4") (pintype "passive"))
    )
    (net (code "62") (name "5V_RAW") (class "Default")
      (node (ref "FB1") (pin "1") (pinfunction "1_1") (pintype "passive"))
      (node (ref "J1") (pin "17") (pinfunction "VCC_17") (pintype "passive"))
      (node (ref "J1") (pin "51") (pinfunction "VCC_51") (pintype "passive"))
    )
    (net (code "63") (name "A5V") (class "Default")
      (node (ref "C15") (pin "2") (pinfunction "2_2") (pintype "passive"))
      (node (ref "C27") (pin "1") (pinfunction "1_1") (pintype "passive"))
      (node (ref "C3") (pin "1") (pinfunction "1_1") (pintype "passive"))
      (node (ref "C4") (pin "1") (pinfunction "1_1") (pintype "passive"))
      (node (ref "L1") (pin "1") (pinfunction "1_1") (pintype "passive"))
      (node (ref "R29") (pin "2") (pinfunction "2_2") (pintype "passive"))
      (node (ref "R33") (pin "2") (pinfunction "2_2") (pintype "passive"))
      (node (ref "R5") (pin "2") (pinfunction "2_2") (pintype "passive"))
      (node (ref "U6") (pin "8") (pinfunction "VDD_8") (pintype "passive"))
      (node (ref "U7") (pin "6") (pinfunction "VCC_6") (pintype "passive"))
      (node (ref "U8") (pin "8") (pinfunction "V+_8") (pintype "passive"))
    )
    (net (code "64") (name "GND") (class "Default")
      (node (ref "C1") (pin "2") (pinfunction "2_2") (pintype "passive"))
      (node (ref "C10") (pin "1") (pinfunction "1_1") (pintype "passive"))
      (node (ref "C14") (pin "1") (pinfunction "1_1") (pintype "passive"))
      (node (ref "C15") (pin "1") (pinfunction "1_1") (pintype "passive"))
      (node (ref "C16") (pin "1") (pinfunction "1_1") (pintype "passive"))
      (node (ref "C17") (pin "1") (pinfunction "1_1") (pintype "passive"))
      (node (ref "C18") (pin "1") (pinfunction "1_1") (pintype "passive"))
      (node (ref "C19") (pin "1") (pinfunction "1_1") (pintype "passive"))
      (node (ref "C2") (pin "2") (pinfunction "2_2") (pintype "passive"))
      (node (ref "C20") (pin "1") (pinfunction "1_1") (pintype "passive"))
      (node (ref "C21") (pin "1") (pinfunction "1_1") (pintype "passive"))
      (node (ref "C22") (pin "2") (pinfunction "2_2") (pintype "passive"))
      (node (ref "C23") (pin "2") (pinfunction "2_2") (pintype "passive"))
      (node (ref "C24") (pin "1") (pinfunction "1_1") (pintype "passive"))
      (node (ref "C27") (pin "2") (pinfunction "2_2") (pintype "passive"))
      (node (ref "C28") (pin "1") (pinfunction "1_1") (pintype "passive"))
      (node (ref "C3") (pin "2") (pinfunction "2_2") (pintype "passive"))
      (node (ref "C4") (pin "2") (pinfunction "2_2") (pintype "passive"))
      (node (ref "C5") (pin "2") (pinfunction "2_2") (pintype "passive"))
      (node (ref "C6") (pin "1") (pinfunction "1_1") (pintype "passive"))
      (node (ref "C9") (pin "2") (pinfunction "2_2") (pintype "passive"))
      (node (ref "J1") (pin "1") (pinfunction "GND_1") (pintype "passive"))
      (node (ref "J1") (pin "34") (pinfunction "GND_34") (pintype "passive"))
      (node (ref "J1") (pin "35") (pinfunction "GND_35") (pintype "passive"))
      (node (ref "J1") (pin "36") (pinfunction "~{CD1}_36") (pintype "passive"))
      (node (ref "J1") (pin "57") (pinfunction "~{VS2}_57") (pintype "passive"))
      (node (ref "J1") (pin "67") (pinfunction "~{CD2}_67") (pintype "passive"))
      (node (ref "J1") (pin "68") (pinfunction "GND_68") (pintype "passive"))
      (node (ref "J2") (pin "1") (pintype "passive"))
      (node (ref "J2") (pin "2") (pintype "passive"))
      (node (ref "Q1") (pin "2") (pinfunction "E_2") (pintype "passive"))
      (node (ref "Q2") (pin "2") (pinfunction "E_2") (pintype "passive"))
      (node (ref "R12") (pin "1") (pinfunction "1_1") (pintype "passive"))
      (node (ref "R17") (pin "1") (pinfunction "1_1") (pintype "passive"))
      (node (ref "R2") (pin "1") (pinfunction "1_1") (pintype "passive"))
      (node (ref "R21") (pin "1") (pinfunction "1_1") (pintype "passive"))
      (node (ref "R26") (pin "1") (pinfunction "1_1") (pintype "passive"))
      (node (ref "R30") (pin "1") (pinfunction "1_1") (pintype "passive"))
      (node (ref "R31") (pin "1") (pinfunction "1_1") (pintype "passive"))
      (node (ref "RP1") (pin "5") (pintype "passive"))
      (node (ref "U1") (pin "7") (pinfunction "GND_7") (pintype "passive"))
      (node (ref "U2") (pin "15") (pinfunction "VSS_15") (pintype "passive"))
      (node (ref "U2") (pin "20") (pinfunction "VSS_20") (pintype "passive"))
      (node (ref "U2") (pin "32") (pinfunction "VSS_32") (pintype "passive"))
      (node (ref "U2") (pin "44") (pinfunction "VSS_44") (pintype "passive"))
      (node (ref "U2") (pin "5") (pinfunction "VSS_5") (pintype "passive"))
      (node (ref "U2") (pin "68") (pinfunction "VSS_68") (pintype "passive"))
      (node (ref "U2") (pin "77") (pinfunction "VSS_77") (pintype "passive"))
      (node (ref "U2") (pin "88") (pinfunction "VSS_88") (pintype "passive"))
      (node (ref "U3") (pin "5") (pinfunction "VSS_5") (pintype "passive"))
      (node (ref "U3") (pin "6") (pinfunction "ORG_6") (pintype "passive"))
      (node (ref "U4") (pin "11") (pinfunction "5A_11") (pintype "passive"))
      (node (ref "U4") (pin "13") (pinfunction "6A_13") (pintype "passive"))
      (node (ref "U4") (pin "3") (pinfunction "2A_3") (pintype "passive"))
      (node (ref "U4") (pin "7") (pinfunction "GND_7") (pintype "passive"))
      (node (ref "U5") (pin "1") (pinfunction "VSS_1") (pintype "passive"))
      (node (ref "U5") (pin "14") (pinfunction "VSS_14") (pintype "passive"))
      (node (ref "U5") (pin "16") (pinfunction "VSS_16") (pintype "passive"))
      (node (ref "U6") (pin "3") (pinfunction "GND_3") (pintype "passive"))
      (node (ref "U7") (pin "7") (pinfunction "GND_7") (pintype "passive"))
      (node (ref "U8") (pin "4") (pinfunction "V-_4") (pintype "passive"))
      (node (ref "UX1") (pin "2") (pinfunction "GND_2") (pintype "passive"))
    )
    (net (code "65") (name "Net-(C2-Pad1)") (class "Default")
      (node (ref "C2") (pin "1") (pinfunction "1_1") (pintype "passive"))
      (node (ref "R1") (pin "1") (pinfunction "1_1") (pintype "passive"))
      (node (ref "R8") (pin "2") (pinfunction "2_2") (pintype "passive"))
    )
    (net (code "66") (name "Net-(C7-Pad1)") (class "Default")
      (node (ref "C7") (pin "1") (pinfunction "1_1") (pintype "passive"))
      (node (ref "R11") (pin "2") (pinfunction "2_2") (pintype "passive"))
      (node (ref "R16") (pin "2") (pinfunction "2_2") (pintype "passive"))
    )
    (net (code "67") (name "Net-(C7-Pad2)") (class "Default")
      (node (ref "C7") (pin "2") (pinfunction "2_2") (pintype "passive"))
      (node (ref "R15") (pin "1") (pinfunction "1_1") (pintype "passive"))
      (node (ref "R17") (pin "2") (pinfunction "2_2") (pintype "passive"))
      (node (ref "R5") (pin "1") (pinfunction "1_1") (pintype "passive"))
    )
    (net (code "68") (name "Net-(C8-Pad2)") (class "Default")
      (node (ref "C8") (pin "2") (pinfunction "2_2") (pintype "passive"))
      (node (ref "R18") (pin "2") (pinfunction "2_2") (pintype "passive"))
      (node (ref "R19") (pin "2") (pinfunction "2_2") (pintype "passive"))
    )
    (net (code "69") (name "Net-(C9-Pad1)") (class "Default")
      (node (ref "C9") (pin "1") (pinfunction "1_1") (pintype "passive"))
      (node (ref "R22") (pin "1") (pinfunction "1_1") (pintype "passive"))
    )
    (net (code "70") (name "Net-(C10-Pad2)") (class "Default")
      (node (ref "C10") (pin "2") (pinfunction "2_2") (pintype "passive"))
      (node (ref "R23") (pin "1") (pinfunction "1_1") (pintype "passive"))
    )
    (net (code "71") (name "Net-(C11-Pad1)") (class "Default")
      (node (ref "C11") (pin "1") (pinfunction "1_1") (pintype "passive"))
      (node (ref "RP1") (pin "4") (pintype "passive"))
    )
    (net (code "72") (name "Net-(C11-Pad2)") (class "Default")
      (node (ref "C11") (pin "2") (pinfunction "2_2") (pintype "passive"))
      (node (ref "R29") (pin "1") (pinfunction "1_1") (pintype "passive"))
      (node (ref "R30") (pin "2") (pinfunction "2_2") (pintype "passive"))
      (node (ref "U8") (pin "3") (pintype "passive"))
    )
    (net (code "73") (name "Net-(C12-Pad1)") (class "Default")
      (node (ref "C12") (pin "1") (pinfunction "1_1") (pintype "passive"))
      (node (ref "RP1") (pin "3") (pintype "passive"))
    )
    (net (code "74") (name "Net-(C12-Pad2)") (class "Default")
      (node (ref "C12") (pin "2") (pinfunction "2_2") (pintype "passive"))
      (node (ref "R31") (pin "2") (pinfunction "2_2") (pintype "passive"))
      (node (ref "R33") (pin "1") (pinfunction "1_1") (pintype "passive"))
      (node (ref "U8") (pin "5") (pintype "passive"))
    )
    (net (code "75") (name "Net-(C13-Pad1)") (class "Default")
      (node (ref "C13") (pin "1") (pinfunction "1_1") (pintype "passive"))
      (node (ref "C26") (pin "1") (pinfunction "1_1") (pintype "passive"))
      (node (ref "R25") (pin "2") (pinfunction "2_2") (pintype "passive"))
      (node (ref "U8") (pin "7") (pintype "passive"))
    )
    (net (code "76") (name "Net-(C13-Pad2)") (class "Default")
      (node (ref "C13") (pin "2") (pinfunction "2_2") (pintype "passive"))
      (node (ref "R27") (pin "2") (pinfunction "2_2") (pintype "passive"))
      (node (ref "R28") (pin "2") (pinfunction "2_2") (pintype "passive"))
    )
    (net (code "77") (name "Net-(C16-Pad2)") (class "Default")
      (node (ref "C16") (pin "2") (pinfunction "2_2") (pintype "passive"))
      (node (ref "J2") (pin "5") (pintype "passive"))
      (node (ref "R11") (pin "1") (pinfunction "1_1") (pintype "passive"))
    )
    (net (code "78") (name "Net-(C23-Pad1)") (class "Default")
      (node (ref "C23") (pin "1") (pinfunction "1_1") (pintype "passive"))
      (node (ref "R14") (pin "2") (pinfunction "2_2") (pintype "passive"))
    )
    (net (code "79") (name "Net-(C25-Pad1)") (class "Default")
      (node (ref "C25") (pin "1") (pinfunction "1_1") (pintype "passive"))
      (node (ref "C8") (pin "1") (pinfunction "1_1") (pintype "passive"))
      (node (ref "R24") (pin "2") (pinfunction "2_2") (pintype "passive"))
      (node (ref "U8") (pin "1") (pintype "passive"))
    )
    (net (code "80") (name "Net-(C25-Pad2)") (class "Default")
      (node (ref "C25") (pin "2") (pinfunction "2_2") (pintype "passive"))
      (node (ref "R22") (pin "2") (pinfunction "2_2") (pintype "passive"))
      (node (ref "R24") (pin "1") (pinfunction "1_1") (pintype "passive"))
      (node (ref "U8") (pin "2") (pintype "passive"))
    )
    (net (code "81") (name "Net-(C26-Pad2)") (class "Default")
      (node (ref "C26") (pin "2") (pinfunction "2_2") (pintype "passive"))
      (node (ref "R23") (pin "2") (pinfunction "2_2") (pintype "passive"))
      (node (ref "R25") (pin "1") (pinfunction "1_1") (pintype "passive"))
      (node (ref "U8") (pin "6") (pintype "passive"))
    )
    (net (code "82") (name "Net-(C28-Pad2)") (class "Default")
      (node (ref "C28") (pin "2") (pinfunction "2_2") (pintype "passive"))
      (node (ref "J2") (pin "6") (pintype "passive"))
      (node (ref "R16") (pin "1") (pinfunction "1_1") (pintype "passive"))
    )
    (net (code "83") (name "Net-(J1-WP{slash}~{IOIS16})") (class "Default")
      (node (ref "J1") (pin "33") (pinfunction "WP/~{IOIS16}_33") (pintype "passive"))
      (node (ref "U2") (pin "10") (pinfunction "PC_WP/~{IOIS16}/~{IOCS16}_10") (pintype "passive"))
    )
    (net (code "84") (name "Net-(Q1-B)") (class "Default")
      (node (ref "Q1") (pin "1") (pinfunction "B_1") (pintype "passive"))
      (node (ref "R10") (pin "1") (pinfunction "1_1") (pintype "passive"))
    )
    (net (code "85") (name "Net-(Q1-C)") (class "Default")
      (node (ref "J2") (pin "4") (pintype "passive"))
      (node (ref "Q1") (pin "3") (pinfunction "C_3") (pintype "passive"))
      (node (ref "R18") (pin "1") (pinfunction "1_1") (pintype "passive"))
      (node (ref "R19") (pin "1") (pinfunction "1_1") (pintype "passive"))
      (node (ref "R21") (pin "2") (pinfunction "2_2") (pintype "passive"))
    )
    (net (code "86") (name "Net-(Q2-B)") (class "Default")
      (node (ref "Q2") (pin "1") (pinfunction "B_1") (pintype "passive"))
      (node (ref "R3") (pin "1") (pinfunction "1_1") (pintype "passive"))
    )
    (net (code "87") (name "Net-(Q2-C)") (class "Default")
      (node (ref "J2") (pin "3") (pintype "passive"))
      (node (ref "Q2") (pin "3") (pinfunction "C_3") (pintype "passive"))
      (node (ref "R26") (pin "2") (pinfunction "2_2") (pintype "passive"))
      (node (ref "R27") (pin "1") (pinfunction "1_1") (pintype "passive"))
      (node (ref "R28") (pin "1") (pinfunction "1_1") (pintype "passive"))
    )
    (net (code "88") (name "Net-(R10-Pad2)") (class "Default")
      (node (ref "R10") (pin "2") (pinfunction "2_2") (pintype "passive"))
      (node (ref "R2") (pin "2") (pinfunction "2_2") (pintype "passive"))
      (node (ref "R3") (pin "2") (pinfunction "2_2") (pintype "passive"))
      (node (ref "R9") (pin "2") (pinfunction "2_2") (pintype "passive"))
    )
    (net (code "89") (name "Net-(U1-1D)") (class "Default")
      (node (ref "U1") (pin "2") (pinfunction "1D_2") (pintype "passive"))
      (node (ref "U1") (pin "6") (pinfunction "1~{Q}_6") (pintype "passive"))
    )
    (net (code "90") (name "Net-(U1-1Q)") (class "Default")
      (node (ref "U1") (pin "5") (pinfunction "1Q_5") (pintype "passive"))
      (node (ref "U2") (pin "58") (pinfunction "PC_MCLK_IN_58") (pintype "passive"))
    )
    (net (code "91") (name "Net-(U1-2CLK)") (class "Default")
      (node (ref "U1") (pin "11") (pinfunction "2CLK_11") (pintype "passive"))
      (node (ref "U4") (pin "2") (pinfunction "1Y_2") (pintype "passive"))
    )
    (net (code "92") (name "Net-(U1-2Q)") (class "Default")
      (node (ref "U1") (pin "9") (pinfunction "2Q_9") (pintype "passive"))
      (node (ref "U5") (pin "11") (pinfunction "~{IC}_11") (pintype "passive"))
    )
    (net (code "93") (name "Net-(U1-2~{CLR})") (class "Default")
      (node (ref "U1") (pin "13") (pinfunction "2~{CLR}_13") (pintype "passive"))
      (node (ref "U2") (pin "11") (pinfunction "~{ATA}_HRESET_11") (pintype "passive"))
    )
    (net (code "94") (name "Net-(U2-EE_CS)") (class "Default")
      (node (ref "U2") (pin "52") (pinfunction "EE_CS_52") (pintype "passive"))
      (node (ref "U3") (pin "1") (pinfunction "S_1") (pintype "passive"))
    )
    (net (code "95") (name "Net-(U2-EE_D0)") (class "Default")
      (node (ref "U2") (pin "53") (pinfunction "EE_D0_53") (pintype "passive"))
      (node (ref "U3") (pin "3") (pinfunction "D_3") (pintype "passive"))
    )
    (net (code "96") (name "Net-(U2-EE_D1)") (class "Default")
      (node (ref "U2") (pin "54") (pinfunction "EE_D1_54") (pintype "passive"))
      (node (ref "U3") (pin "4") (pinfunction "Q_4") (pintype "passive"))
    )
    (net (code "97") (name "Net-(U2-EE_MASTER)") (class "Default")
      (node (ref "R7") (pin "1") (pinfunction "1_1") (pintype "passive"))
      (node (ref "U2") (pin "51") (pinfunction "EE_MASTER_51") (pintype "passive"))
    )
    (net (code "98") (name "Net-(U2-EE_SK)") (class "Default")
      (node (ref "U2") (pin "50") (pinfunction "EE_SK_50") (pintype "passive"))
      (node (ref "U3") (pin "2") (pinfunction "C_2") (pintype "passive"))
    )
    (net (code "99") (name "Net-(U2-EXTP_AUDIO)") (class "Default")
      (node (ref "R4") (pin "1") (pinfunction "1_1") (pintype "passive"))
      (node (ref "U2") (pin "60") (pinfunction "EXTP_AUDIO_60") (pintype "passive"))
    )
    (net (code "100") (name "Net-(U2-~{POR})") (class "Default")
      (node (ref "C19") (pin "2") (pinfunction "2_2") (pintype "passive"))
      (node (ref "U2") (pin "56") (pinfunction "~{POR}_56") (pintype "passive"))
    )
    (net (code "101") (name "Net-(U4-3A)") (class "Default")
      (node (ref "R1") (pin "2") (pinfunction "2_2") (pintype "passive"))
      (node (ref "U4") (pin "5") (pinfunction "3A_5") (pintype "passive"))
    )
    (net (code "102") (name "Net-(U4-3Y)") (class "Default")
      (node (ref "R9") (pin "1") (pinfunction "1_1") (pintype "passive"))
      (node (ref "U4") (pin "6") (pinfunction "3Y_6") (pintype "passive"))
    )
    (net (code "103") (name "Net-(U6-L.OUT)") (class "Default")
      (node (ref "RP1") (pin "1") (pintype "passive"))
      (node (ref "U6") (pin "4") (pinfunction "L.OUT_4") (pintype "passive"))
    )
    (net (code "104") (name "Net-(U6-R.OUT)") (class "Default")
      (node (ref "RP1") (pin "2") (pintype "passive"))
      (node (ref "U6") (pin "1") (pinfunction "R.OUT_1") (pintype "passive"))
    )
    (net (code "105") (name "Net-(U6-REF)") (class "Default")
      (node (ref "C5") (pin "1") (pinfunction "1_1") (pintype "passive"))
      (node (ref "U6") (pin "2") (pinfunction "REF_2") (pintype "passive"))
    )
    (net (code "106") (name "Net-(U7-Bypass)") (class "Default")
      (node (ref "C24") (pin "2") (pinfunction "2_2") (pintype "passive"))
      (node (ref "U7") (pin "2") (pinfunction "Bypass_2") (pintype "passive"))
    )
    (net (code "107") (name "Net-(U7-INN)") (class "Default")
      (node (ref "R14") (pin "1") (pinfunction "1_1") (pintype "passive"))
      (node (ref "U7") (pin "4") (pinfunction "INN_4") (pintype "passive"))
    )
    (net (code "108") (name "Net-(U7-INP)") (class "Default")
      (node (ref "R15") (pin "2") (pinfunction "2_2") (pintype "passive"))
      (node (ref "U7") (pin "3") (pinfunction "INP_3") (pintype "passive"))
    )
    (net (code "109") (name "Net-(U7-VoN)") (class "Default")
      (node (ref "N_LS1") (pin "1") (pintype "passive"))
      (node (ref "U7") (pin "5") (pinfunction "VoN_5") (pintype "passive"))
    )
    (net (code "110") (name "Net-(U7-VoP)") (class "Default")
      (node (ref "N_LS2") (pin "1") (pintype "passive"))
      (node (ref "U7") (pin "8") (pinfunction "VoP_8") (pintype "passive"))
    )
    (net (code "111") (name "Net-(UX1-EN)") (class "Default")
      (node (ref "R12") (pin "2") (pinfunction "2_2") (pintype "passive"))
      (node (ref "UX1") (pin "1") (pinfunction "EN_1") (pintype "passive"))
    )
    (net (code "112") (name "unconnected-(J1-A11-Pad10)") (class "Default")
      (node (ref "J1") (pin "10") (pinfunction "A11_10") (pintype "passive+no_connect"))
    )
    (net (code "113") (name "unconnected-(J1-A12-Pad21)") (class "Default")
      (node (ref "J1") (pin "21") (pinfunction "A12_21") (pintype "passive+no_connect"))
    )
    (net (code "114") (name "unconnected-(J1-A13-Pad13)") (class "Default")
      (node (ref "J1") (pin "13") (pinfunction "A13_13") (pintype "passive+no_connect"))
    )
    (net (code "115") (name "unconnected-(J1-A14-Pad14)") (class "Default")
      (node (ref "J1") (pin "14") (pinfunction "A14_14") (pintype "passive+no_connect"))
    )
    (net (code "116") (name "unconnected-(J1-A15-Pad20)") (class "Default")
      (node (ref "J1") (pin "20") (pinfunction "A15_20") (pintype "passive+no_connect"))
    )
    (net (code "117") (name "unconnected-(J1-A16-Pad19)") (class "Default")
      (node (ref "J1") (pin "19") (pinfunction "A16_19") (pintype "passive+no_connect"))
    )
    (net (code "118") (name "unconnected-(J1-A17-Pad46)") (class "Default")
      (node (ref "J1") (pin "46") (pinfunction "A17_46") (pintype "passive+no_connect"))
    )
    (net (code "119") (name "unconnected-(J1-A18-Pad47)") (class "Default")
      (node (ref "J1") (pin "47") (pinfunction "A18_47") (pintype "passive+no_connect"))
    )
    (net (code "120") (name "unconnected-(J1-A19-Pad48)") (class "Default")
      (node (ref "J1") (pin "48") (pinfunction "A19_48") (pintype "passive+no_connect"))
    )
    (net (code "121") (name "unconnected-(J1-A20-Pad49)") (class "Default")
      (node (ref "J1") (pin "49") (pinfunction "A20_49") (pintype "passive+no_connect"))
    )
    (net (code "122") (name "unconnected-(J1-A21-Pad50)") (class "Default")
      (node (ref "J1") (pin "50") (pinfunction "A21_50") (pintype "passive+no_connect"))
    )
    (net (code "123") (name "unconnected-(J1-A22-Pad53)") (class "Default")
      (node (ref "J1") (pin "53") (pinfunction "A22_53") (pintype "passive+no_connect"))
    )
    (net (code "124") (name "unconnected-(J1-A23-Pad54)") (class "Default")
      (node (ref "J1") (pin "54") (pinfunction "A23_54") (pintype "passive+no_connect"))
    )
    (net (code "125") (name "unconnected-(J1-A24-Pad55)") (class "Default")
      (node (ref "J1") (pin "55") (pinfunction "A24_55") (pintype "passive+no_connect"))
    )
    (net (code "126") (name "unconnected-(J1-A25-Pad56)") (class "Default")
      (node (ref "J1") (pin "56") (pinfunction "A25_56") (pintype "passive+no_connect"))
    )
    (net (code "127") (name "unconnected-(J1-VPP1-Pad18)") (class "Default")
      (node (ref "J1") (pin "18") (pinfunction "VPP1_18") (pintype "passive+no_connect"))
    )
    (net (code "128") (name "unconnected-(J1-VPP2-Pad52)") (class "Default")
      (node (ref "J1") (pin "52") (pinfunction "VPP2_52") (pintype "passive+no_connect"))
    )
    (net (code "129") (name "unconnected-(J1-~{BVD2}{slash}SPKR-Pad62)") (class "Default")
      (node (ref "J1") (pin "62") (pinfunction "~{BVD2}/SPKR_62") (pintype "passive+no_connect"))
    )
    (net (code "130") (name "unconnected-(J1-~{VS1}-Pad43)") (class "Default")
      (node (ref "J1") (pin "43") (pinfunction "~{VS1}_43") (pintype "passive+no_connect"))
    )
    (net (code "131") (name "unconnected-(U1-2~{Q}-Pad8)") (class "Default")
      (node (ref "U1") (pin "8") (pinfunction "2~{Q}_8") (pintype "passive+no_connect"))
    )
    (net (code "132") (name "unconnected-(U2-ATA_DATA8{slash}RES1-Pad13)") (class "Default")
      (node (ref "U2") (pin "13") (pinfunction "ATA_DATA8/RES1_13") (pintype "passive+no_connect"))
    )
    (net (code "133") (name "unconnected-(U2-ATA_DATA9{slash}PACK_IN-Pad17)") (class "Default")
      (node (ref "U2") (pin "17") (pinfunction "ATA_DATA9/PACK_IN_17") (pintype "passive+no_connect"))
    )
    (net (code "134") (name "unconnected-(U2-ATA_DATA10-Pad19)") (class "Default")
      (node (ref "U2") (pin "19") (pinfunction "ATA_DATA10_19") (pintype "passive+no_connect"))
    )
    (net (code "135") (name "unconnected-(U2-ATA_DATA11-Pad22)") (class "Default")
      (node (ref "U2") (pin "22") (pinfunction "ATA_DATA11_22") (pintype "passive+no_connect"))
    )
    (net (code "136") (name "unconnected-(U2-ATA_DATA12-Pad25)") (class "Default")
      (node (ref "U2") (pin "25") (pinfunction "ATA_DATA12_25") (pintype "passive+no_connect"))
    )
    (net (code "137") (name "unconnected-(U2-ATA_DATA13-Pad27)") (class "Default")
      (node (ref "U2") (pin "27") (pinfunction "ATA_DATA13_27") (pintype "passive+no_connect"))
    )
    (net (code "138") (name "unconnected-(U2-ATA_DATA14-Pad29)") (class "Default")
      (node (ref "U2") (pin "29") (pinfunction "ATA_DATA14_29") (pintype "passive+no_connect"))
    )
    (net (code "139") (name "unconnected-(U2-ATA_DATA15-Pad31)") (class "Default")
      (node (ref "U2") (pin "31") (pinfunction "ATA_DATA15_31") (pintype "passive+no_connect"))
    )
    (net (code "140") (name "unconnected-(U2-ATA_HA2-Pad41)") (class "Default")
      (node (ref "U2") (pin "41") (pinfunction "ATA_HA2_41") (pintype "passive+no_connect"))
    )
    (net (code "141") (name "unconnected-(U2-ATA_HCS1-Pad43)") (class "Default")
      (node (ref "U2") (pin "43") (pinfunction "ATA_HCS1_43") (pintype "passive+no_connect"))
    )
    (net (code "142") (name "unconnected-(U2-ATA_IOCHRDY-Pad35)") (class "Default")
      (node (ref "U2") (pin "35") (pinfunction "ATA_IOCHRDY_35") (pintype "passive+no_connect"))
    )
    (net (code "143") (name "unconnected-(U2-EXTP_APWDN-Pad59)") (class "Default")
      (node (ref "U2") (pin "59") (pinfunction "EXTP_APWDN_59") (pintype "passive+no_connect"))
    )
    (net (code "144") (name "unconnected-(U2-EXTP_STSCHG{slash}RES2-Pad61)") (class "Default")
      (node (ref "U2") (pin "61") (pinfunction "EXTP_STSCHG/RES2_61") (pintype "passive+no_connect"))
    )
    (net (code "145") (name "unconnected-(U2-V_PINT-Pad57)") (class "Default")
      (node (ref "U2") (pin "57") (pinfunction "V_PINT_57") (pintype "passive+no_connect"))
    )
    (net (code "146") (name "unconnected-(U2-~{ATA}_DACK{slash}BVD2-Pad47)") (class "Default")
      (node (ref "U2") (pin "47") (pinfunction "~{ATA}_DACK/BVD2_47") (pintype "passive+no_connect"))
    )
    (net (code "147") (name "unconnected-(U2-~{ATA}_DREQ{slash}BVD1-Pad48)") (class "Default")
      (node (ref "U2") (pin "48") (pinfunction "~{ATA}_DREQ/BVD1_48") (pintype "passive+no_connect"))
    )
    (net (code "148") (name "unconnected-(U2-~{ATA}_IOCS16-Pad37)") (class "Default")
      (node (ref "U2") (pin "37") (pinfunction "~{ATA}_IOCS16_37") (pintype "passive+no_connect"))
    )
    (net (code "149") (name "unconnected-(U2-~{ATA}_MRD-Pad49)") (class "Default")
      (node (ref "U2") (pin "49") (pinfunction "~{ATA}_MRD_49") (pintype "passive+no_connect"))
    )
    (net (code "150") (name "unconnected-(U2-~{ATA}_MWR-Pad55)") (class "Default")
      (node (ref "U2") (pin "55") (pinfunction "~{ATA}_MWR_55") (pintype "passive+no_connect"))
    )
    (net (code "151") (name "unconnected-(U2-~{ATA}_PDASP{slash}EXTP_WP-Pad46)") (class "Default")
      (node (ref "U2") (pin "46") (pinfunction "~{ATA}_PDASP/EXTP_WP_46") (pintype "passive+no_connect"))
    )
    (net (code "152") (name "unconnected-(U2-~{ATA}_PDIAG{slash}ATA_BHE{slash}RING_IN-Pad45)") (class "Default")
      (node (ref "U2") (pin "45") (pinfunction "~{ATA}_PDIAG/ATA_BHE/RING_IN_45") (pintype "passive+no_connect"))
    )
    (net (code "153") (name "unconnected-(U3-DU-Pad7)") (class "Default")
      (node (ref "U3") (pin "7") (pinfunction "DU_7") (pintype "passive+no_connect"))
    )
    (net (code "154") (name "unconnected-(U4-2Y-Pad4)") (class "Default")
      (node (ref "U4") (pin "4") (pinfunction "2Y_4") (pintype "passive+no_connect"))
    )
    (net (code "155") (name "unconnected-(U4-5Y-Pad10)") (class "Default")
      (node (ref "U4") (pin "10") (pinfunction "5Y_10") (pintype "passive+no_connect"))
    )
    (net (code "156") (name "unconnected-(U4-6Y-Pad12)") (class "Default")
      (node (ref "U4") (pin "12") (pinfunction "6Y_12") (pintype "passive+no_connect"))
    )
    (net (code "157") (name "unconnected-(U5-NC-Pad10)") (class "Default")
      (node (ref "U5") (pin "10") (pinfunction "NC_10") (pintype "passive+no_connect"))
    )
    (net (code "158") (name "unconnected-(U5-NC-Pad13)") (class "Default")
      (node (ref "U5") (pin "13") (pinfunction "NC_13") (pintype "passive+no_connect"))
    )
  )
)
